# Wire_Detector_Schematics.net
KiCad netlist of a schematic drawn in Altium Designer
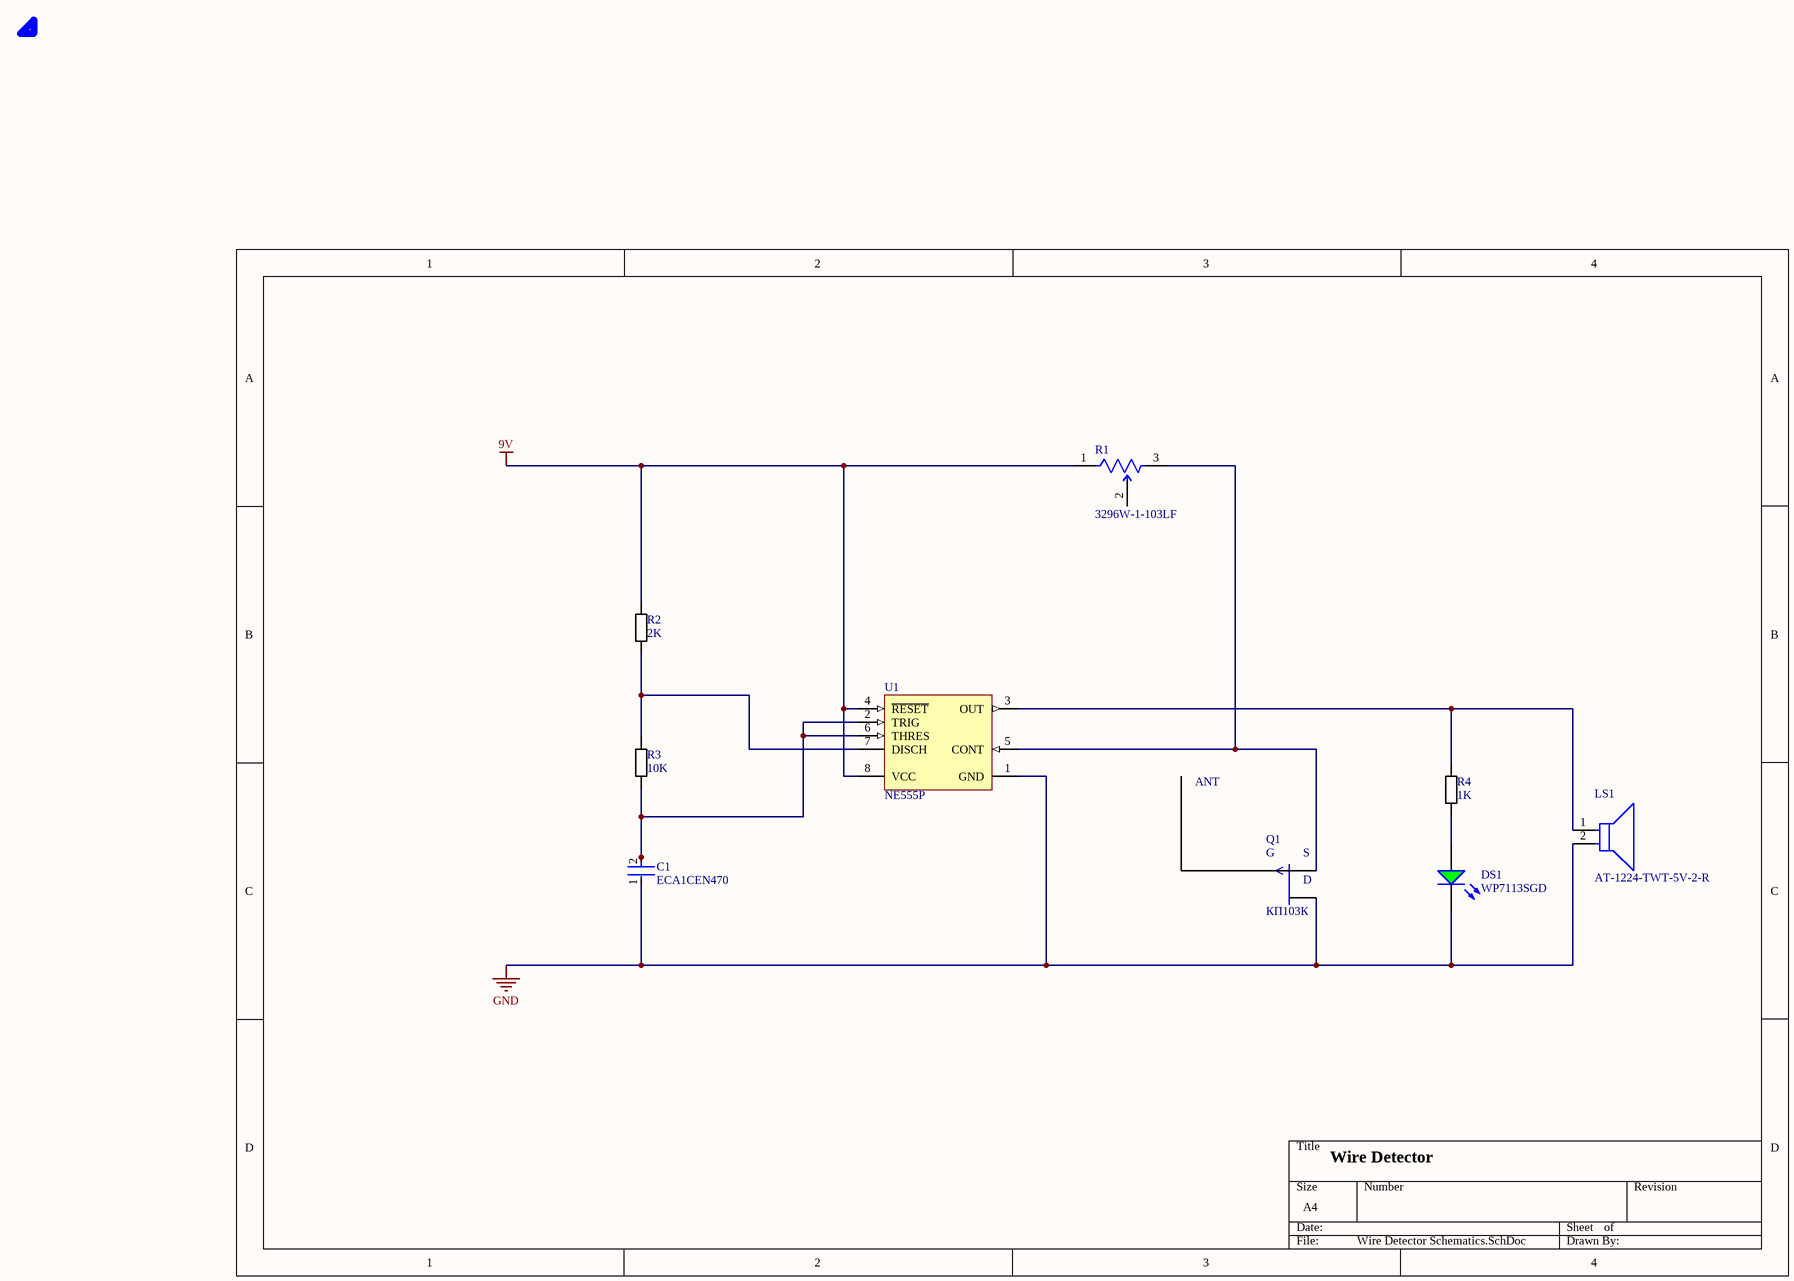
[diagram p0: Wire Detector Schematics.SchDoc]

(export (version "E")
  (design (tool "Eeschema 10.0.6"))
  (components
    (comp (ref "C1")
      (value "ECA1CEN470")
      (footprint "FP-RAD-TH-D_6_3_0_5-L_11-MFG")
      (description "Aluminum Electrolytic Capacitors (Radial Lead Type) 47uF ±20% 16V")
      (fields (field (name "TOLERANCE") "20%"))
      (libsource (lib "Altium Content Vault") (part "f23184f103b6ebe33a8c269c53dcba6"))
    )
    (comp (ref "DS1")
      (value "WP7113SGD")
      (footprint "KING-WP7113SGD_V")
      (description "LED Green, 62.5 mW, 25 mA, -40 to 85 degC, 2-Pin THD, RoHS, Bulk")
      (fields (field (name "MANUFACTURER") "Kingbright"))
      (libsource (lib "Altium Content Vault") (part "LED-GREEN-AK-2"))
    )
    (comp (ref "LS1")
      (value "AT-1224-TWT-5V-2-R")
      (footprint "FP-AT-1224-TWT-5V-2-R-MFG")
      (description "BUZZER MAGNETIC 5V 12MM TH")
      (libsource (lib "Altium Content Vault") (part "1973c4b650225fd2ddacaff6b763965"))
    )
    (comp (ref "Q1")
      (value "КП103К")
      (footprint "TO127P584H533-3")
      (description "JFET P-Channel 10V 0.038W Through Hole TO-18")
      (fields (field (name "MF") "Motorola") (field (name "MP") "2N2608"))
      (libsource (lib "2N2608") (part "2N2608"))
    )
    (comp (ref "R1")
      (value "3296W-1-103LF")
      (footprint "FP-3296W-MFG")
      (description "TRIMMER 10K OHM 0.5W PC PIN TOP")
      (fields (field (name "TOLERANCE") "10%"))
      (libsource (lib "Altium Content Vault") (part "2dcfd2547301a7d3209a5e99acfd772"))
    )
    (comp (ref "R2")
      (value "2K")
      (footprint "R")
      (description "1 kOhms ±1% 0.25W, 1/4W Through Hole Resistor Axial Automotive AEC-Q200 Metal Film")
      (fields (field (name "VOLTAGE") "250V") (field (name "MPN") "MFS1/4CC1001F"))
      (libsource (lib "R 0,250W") (part "R 0,250W"))
    )
    (comp (ref "R3")
      (value "10K")
      (footprint "R")
      (description "1 kOhms ±1% 0.25W, 1/4W Through Hole Resistor Axial Automotive AEC-Q200 Metal Film")
      (fields (field (name "VOLTAGE") "250V") (field (name "MPN") "MFS1/4CC1001F"))
      (libsource (lib "R 0,250W") (part "R 0,250W"))
    )
    (comp (ref "R4")
      (value "1K")
      (footprint "R")
      (description "1 kOhms ±1% 0.25W, 1/4W Through Hole Resistor Axial Automotive AEC-Q200 Metal Film")
      (fields (field (name "VOLTAGE") "250V") (field (name "MPN") "MFS1/4CC1001F"))
      (libsource (lib "R 0,250W") (part "R 0,250W"))
    )
    (comp (ref "U1")
      (value "NE555P")
      (footprint "P0008A")
      (description "Precision Timer, 4.5 to 16 V, 0 to 70 degC, 8-Pin DIP, Pb-Free, Tube")
      (fields (field (name "MANUFACTURER") "TexasInstruments"))
      (libsource (lib "Altium Content Vault") (part "TI-NE555-P8"))
    )
  )
  (nets
    (net (code "1") (name "9V") (class "Default")
      (node (ref "R1") (pin "1") (pinfunction "CCW_1") (pintype "passive"))
      (node (ref "R2") (pin "2") (pinfunction "2_2") (pintype "passive"))
      (node (ref "U1") (pin "4") (pinfunction "~{RESET}_4") (pintype "input"))
      (node (ref "U1") (pin "8") (pinfunction "VCC_8") (pintype "power_in"))
    )
    (net (code "2") (name "GND") (class "Default")
      (node (ref "C1") (pin "1") (pinfunction "1_1") (pintype "passive"))
      (node (ref "DS1") (pin "2") (pinfunction "K_2") (pintype "passive"))
      (node (ref "LS1") (pin "2") (pinfunction "A_2") (pintype "passive"))
      (node (ref "Q1") (pin "3") (pinfunction "D_3") (pintype "passive"))
      (node (ref "U1") (pin "1") (pinfunction "GND_1") (pintype "power_in"))
    )
    (net (code "3") (name "Net-(DS1-A)") (class "Default")
      (node (ref "DS1") (pin "1") (pinfunction "A_1") (pintype "passive"))
      (node (ref "R4") (pin "1") (pinfunction "1_1") (pintype "passive"))
    )
    (net (code "4") (name "Net-(LS1-C)") (class "Default")
      (node (ref "LS1") (pin "1") (pinfunction "C_1") (pintype "passive"))
      (node (ref "R4") (pin "2") (pinfunction "2_2") (pintype "passive"))
      (node (ref "U1") (pin "3") (pinfunction "OUT_3") (pintype "output"))
    )
    (net (code "5") (name "Net-(Q1-S)") (class "Default")
      (node (ref "Q1") (pin "1") (pinfunction "S_1") (pintype "passive"))
      (node (ref "R1") (pin "3") (pinfunction "CW_3") (pintype "passive"))
      (node (ref "U1") (pin "5") (pinfunction "CONT_5") (pintype "input"))
    )
    (net (code "6") (name "Net-(U1-DISCH)") (class "Default")
      (node (ref "R2") (pin "1") (pinfunction "1_1") (pintype "passive"))
      (node (ref "R3") (pin "2") (pinfunction "2_2") (pintype "passive"))
      (node (ref "U1") (pin "7") (pinfunction "DISCH_7") (pintype "open_collector"))
    )
    (net (code "7") (name "Net-(U1-THRES)") (class "Default")
      (node (ref "C1") (pin "2") (pinfunction "2_2") (pintype "passive"))
      (node (ref "R3") (pin "1") (pinfunction "1_1") (pintype "passive"))
      (node (ref "U1") (pin "2") (pinfunction "TRIG_2") (pintype "input"))
      (node (ref "U1") (pin "6") (pinfunction "THRES_6") (pintype "input"))
    )
    (net (code "8") (name "unconnected-(Q1-G-Pad2)") (class "Default")
      (node (ref "Q1") (pin "2") (pinfunction "G_2") (pintype "passive"))
    )
    (net (code "9") (name "unconnected-(R1-WIPER-Pad2)") (class "Default")
      (node (ref "R1") (pin "2") (pinfunction "WIPER_2") (pintype "passive"))
    )
  )
)
